# MLX90393_breakout1_short.net
KiCad netlist of a schematic drawn in EAGLE
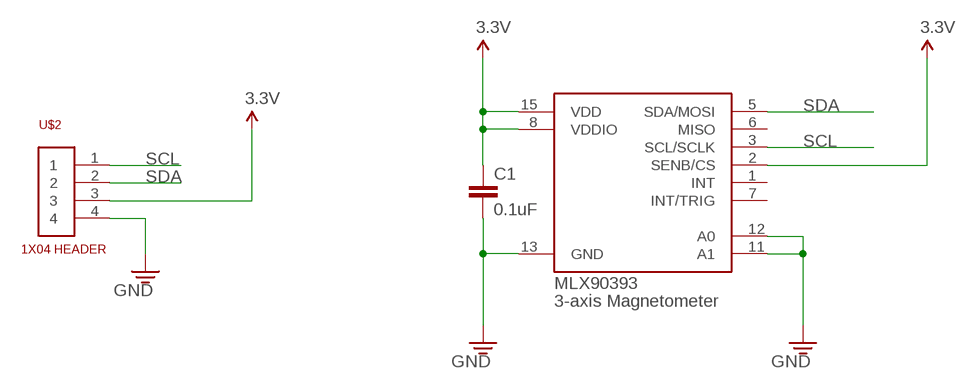
[diagram p0: schematic, sheet 1]

(export (version "E")
  (design (tool "Eeschema 10.0.6"))
  (components
    (comp (ref "C1")
      (value "0.1uF")
      (footprint "eagle-import:0603")
      (libsource (lib "eagle-import") (part "CAP0603"))
    )
    (comp (ref "U$1")
      (value "MLX90393")
      (footprint "eagle-import:16-QFN")
      (libsource (lib "eagle-import") (part "MLX90393"))
    )
    (comp (ref "U$2")
      (value "1X04")
      (footprint "eagle-import:1X04")
      (libsource (lib "eagle-import") (part "1X04"))
    )
  )
  (nets
    (net (code "1") (name "/SCL") (class "Default")
      (node (ref "U$1") (pin "3") (pinfunction "SCL/SCLK_3") (pintype "bidirectional"))
      (node (ref "U$2") (pin "1") (pinfunction "1_1") (pintype "bidirectional"))
    )
    (net (code "2") (name "/SDA") (class "Default")
      (node (ref "U$1") (pin "5") (pinfunction "SDA/MOSI_5") (pintype "bidirectional"))
      (node (ref "U$2") (pin "2") (pinfunction "2_2") (pintype "bidirectional"))
    )
    (net (code "3") (name "3.3V") (class "Default")
      (node (ref "C1") (pin "1") (pinfunction "1_1") (pintype "passive"))
      (node (ref "U$1") (pin "15") (pinfunction "VDD_15") (pintype "bidirectional"))
      (node (ref "U$1") (pin "2") (pinfunction "SENB/CS_2") (pintype "bidirectional"))
      (node (ref "U$1") (pin "8") (pinfunction "VDDIO_8") (pintype "bidirectional"))
      (node (ref "U$2") (pin "3") (pinfunction "3_3") (pintype "bidirectional"))
    )
    (net (code "4") (name "GND") (class "Default")
      (node (ref "C1") (pin "2") (pinfunction "2_2") (pintype "passive"))
      (node (ref "U$1") (pin "11") (pinfunction "A1_11") (pintype "bidirectional"))
      (node (ref "U$1") (pin "12") (pinfunction "A0_12") (pintype "bidirectional"))
      (node (ref "U$1") (pin "13") (pinfunction "GND_13") (pintype "bidirectional"))
      (node (ref "U$2") (pin "4") (pinfunction "4_4") (pintype "bidirectional"))
    )
    (net (code "5") (name "unconnected-(U$1-INT-Pad1)") (class "Default")
      (node (ref "U$1") (pin "1") (pinfunction "INT_1") (pintype "bidirectional"))
    )
    (net (code "6") (name "unconnected-(U$1-INT{slash}TRIG-Pad7)") (class "Default")
      (node (ref "U$1") (pin "7") (pinfunction "INT/TRIG_7") (pintype "bidirectional"))
    )
    (net (code "7") (name "unconnected-(U$1-MISO-Pad6)") (class "Default")
      (node (ref "U$1") (pin "6") (pinfunction "MISO_6") (pintype "bidirectional"))
    )
  )
)
